# Servo_Outputs.net
KiCad netlist of a schematic drawn in Altium Designer
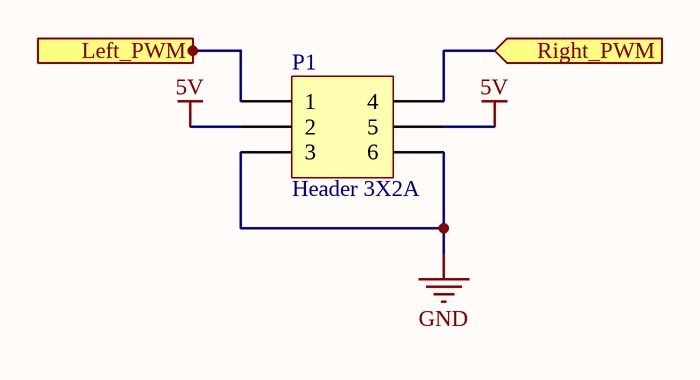
[diagram p0: Servo_Outputs.SchDoc]

(export (version "E")
  (design (tool "Eeschema 10.0.6"))
  (components
    (comp (ref "P1")
      (value "Header 3X2A")
      (footprint "HDR2X3_CEN")
      (description "Header, 3-Pin, Dual row")
      (fields (field (name "PUBLISHER") "Altium Limited"))
      (libsource (lib "PWr in Space team") (part "Header 3X2A"))
    )
  )
  (nets
    (net (code "1") (name "/Left_PWM") (class "Default")
      (node (ref "P1") (pin "1") (pinfunction "1_1") (pintype "passive"))
    )
    (net (code "2") (name "/Right_PWM") (class "Default")
      (node (ref "P1") (pin "4") (pinfunction "4_4") (pintype "passive"))
    )
    (net (code "3") (name "5V") (class "Default")
      (node (ref "P1") (pin "2") (pinfunction "2_2") (pintype "passive"))
      (node (ref "P1") (pin "5") (pinfunction "5_5") (pintype "passive"))
    )
    (net (code "4") (name "GND") (class "Default")
      (node (ref "P1") (pin "3") (pinfunction "3_3") (pintype "passive"))
      (node (ref "P1") (pin "6") (pinfunction "6_6") (pintype "passive"))
    )
  )
)
